# MCU_Design.net
KiCad netlist of a schematic drawn in EAGLE
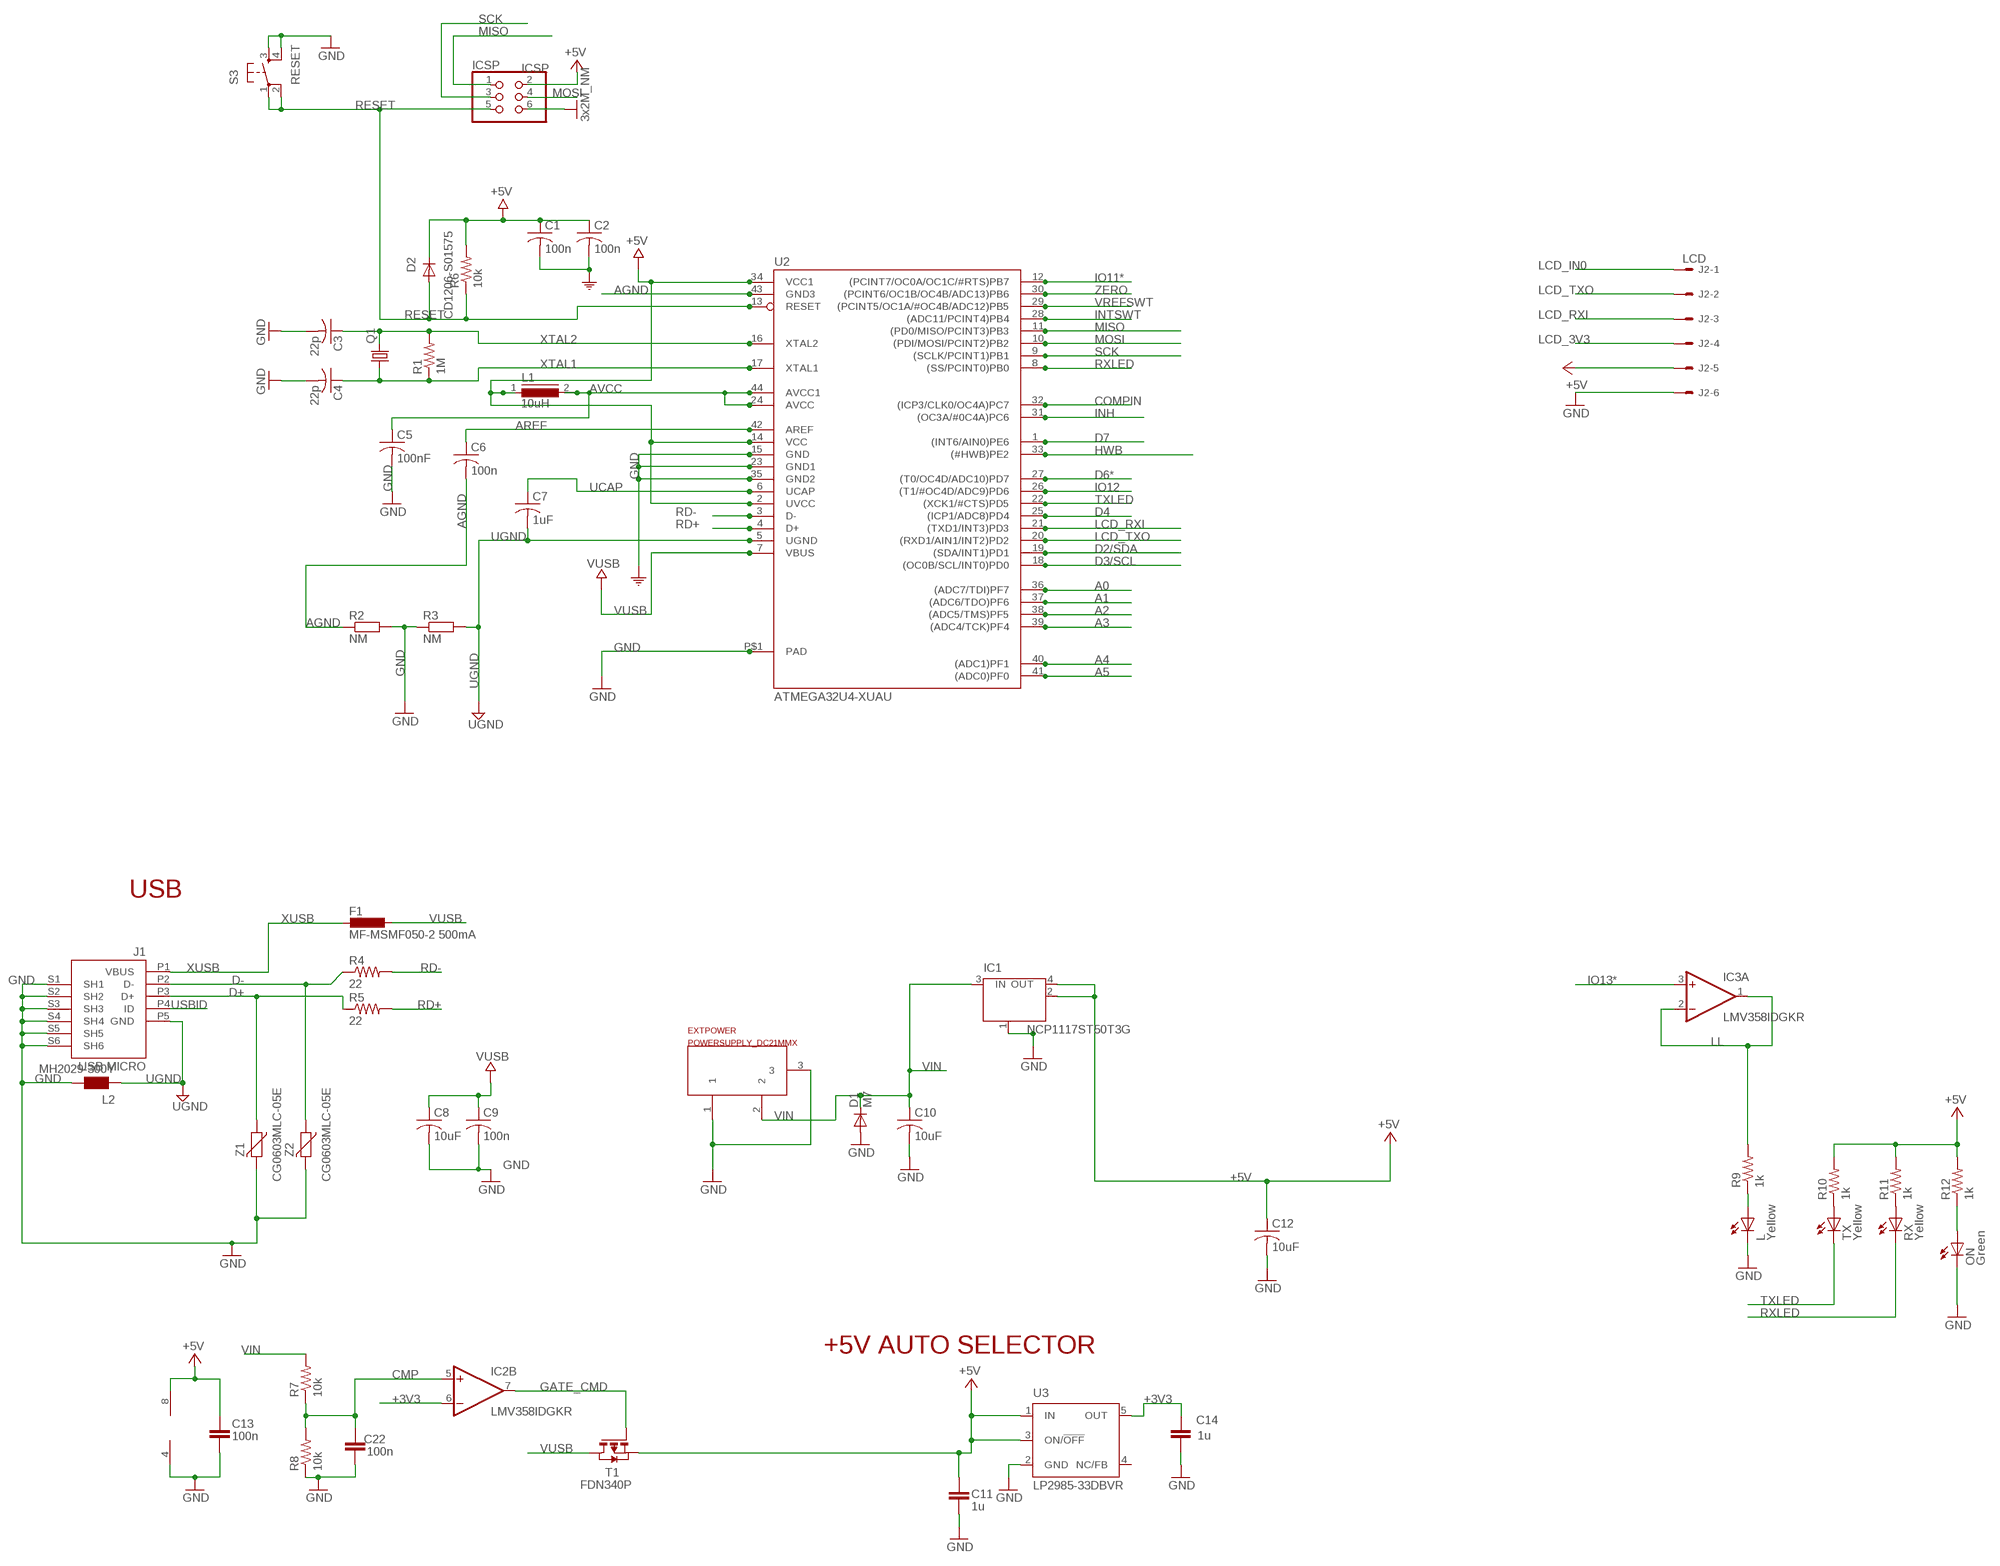
[diagram p0: schematic, sheet 1]

(export (version "E")
  (design (tool "Eeschema 10.0.6"))
  (components
    (comp (ref "C1")
      (value "100n")
      (footprint "eagle-import:C0805")
      (libsource (lib "eagle-import") (part "C-USC0805"))
    )
    (comp (ref "C2")
      (value "100n")
      (footprint "eagle-import:C0805")
      (libsource (lib "eagle-import") (part "C-USC0805"))
    )
    (comp (ref "C3")
      (value "22p")
      (footprint "eagle-import:C0805")
      (libsource (lib "eagle-import") (part "C-USC0805"))
    )
    (comp (ref "C4")
      (value "22p")
      (footprint "eagle-import:C0805")
      (libsource (lib "eagle-import") (part "C-USC0805"))
    )
    (comp (ref "C5")
      (value "100nF")
      (footprint "eagle-import:C0805")
      (libsource (lib "eagle-import") (part "C-USC0805"))
    )
    (comp (ref "C6")
      (value "100n")
      (footprint "eagle-import:C0805")
      (libsource (lib "eagle-import") (part "C-USC0805"))
    )
    (comp (ref "C7")
      (value "1uF")
      (footprint "eagle-import:C0805")
      (libsource (lib "eagle-import") (part "C-USC0805"))
    )
    (comp (ref "C8")
      (value "10uF")
      (footprint "eagle-import:C0805")
      (libsource (lib "eagle-import") (part "C-USC0805"))
    )
    (comp (ref "C9")
      (value "100n")
      (footprint "eagle-import:C0805")
      (libsource (lib "eagle-import") (part "C-USC0805"))
    )
    (comp (ref "C10")
      (value "10uF")
      (footprint "eagle-import:C0805")
      (libsource (lib "eagle-import") (part "C-USC0805"))
    )
    (comp (ref "C11")
      (value "1u")
      (footprint "eagle-import:C0603-ROUND")
      (libsource (lib "eagle-import") (part "C-EUC0603"))
    )
    (comp (ref "C12")
      (value "10uF")
      (footprint "eagle-import:C0805")
      (libsource (lib "eagle-import") (part "C-USC0805"))
    )
    (comp (ref "C13")
      (value "100n")
      (footprint "eagle-import:C0603-ROUND")
      (libsource (lib "eagle-import") (part "C-EUC0603"))
    )
    (comp (ref "C14")
      (value "1u")
      (footprint "eagle-import:C0603-ROUND")
      (libsource (lib "eagle-import") (part "C-EUC0603"))
    )
    (comp (ref "C22")
      (value "100n")
      (footprint "eagle-import:C0603-ROUND")
      (libsource (lib "eagle-import") (part "C-EUC0603"))
    )
    (comp (ref "D1")
      (value "M7")
      (footprint "eagle-import:SMB")
      (libsource (lib "eagle-import") (part "DIODE-SMB"))
    )
    (comp (ref "D2")
      (value "CD1206-S01575")
      (footprint "eagle-import:MINIMELF")
      (libsource (lib "eagle-import") (part "DIODE-MINIMELF"))
    )
    (comp (ref "EXTPOWER")
      (value "POWERSUPPLY_DC21MMX")
      (footprint "eagle-import:POWERSUPPLY_DC-21MM")
      (libsource (lib "eagle-import") (part "POWERSUPPLY_DC21MMX"))
    )
    (comp (ref "F1")
      (value "MF-MSMF050-2 500mA")
      (footprint "eagle-import:L1812")
      (libsource (lib "eagle-import") (part "L-EUL1812"))
    )
    (comp (ref "IC1")
      (value "NCP1117ST50T3G")
      (footprint "eagle-import:SOT223")
      (libsource (lib "eagle-import") (part "MC33269ST-3.3T3"))
    )
    (comp (ref "IC2")
      (value "LMV358IDGKR")
      (footprint "eagle-import:MSOP08")
      (libsource (lib "eagle-import") (part "LMV358?MMX"))
    )
    (comp (ref "IC3")
      (value "LMV358IDGKR")
      (footprint "eagle-import:MSOP08")
      (libsource (lib "eagle-import") (part "LMV358?MMX"))
    )
    (comp (ref "ICSP")
      (value "ICSP")
      (footprint "eagle-import:2X03")
      (libsource (lib "eagle-import") (part "PINHD-2X3"))
    )
    (comp (ref "J1")
      (value "USB MICRO")
      (footprint "eagle-import:CON2_USB_MICRO_B_AT")
      (libsource (lib "eagle-import") (part "MYCON2_USB-MINI-B"))
    )
    (comp (ref "J2")
      (value "LCD")
      (footprint "eagle-import:7395-06")
      (libsource (lib "eagle-import") (part "22-?-0605-7068"))
    )
    (comp (ref "L")
      (value "Yellow")
      (footprint "eagle-import:CHIPLED_0805")
      (libsource (lib "eagle-import") (part "LEDCHIPLED_0805"))
    )
    (comp (ref "L1")
      (value "10uH")
      (footprint "eagle-import:LBC15A")
      (libsource (lib "eagle-import") (part "LBC15A"))
    )
    (comp (ref "L2")
      (value "MH2029-300Y")
      (footprint "eagle-import:0805")
      (libsource (lib "eagle-import") (part "WE-CBF_0805"))
    )
    (comp (ref "ON")
      (value "Green")
      (footprint "eagle-import:CHIPLED_0805")
      (libsource (lib "eagle-import") (part "LEDCHIPLED_0805"))
    )
    (comp (ref "Q1")
      (value "CRYSTALHC49UP")
      (footprint "eagle-import:HC49UP")
      (libsource (lib "eagle-import") (part "CRYSTALHC49UP"))
    )
    (comp (ref "R1")
      (value "1M")
      (footprint "eagle-import:R0805")
      (libsource (lib "eagle-import") (part "R-US_R0805"))
    )
    (comp (ref "R2")
      (value "NM")
      (footprint "eagle-import:R0402")
      (libsource (lib "eagle-import") (part "R-EU_R0402"))
    )
    (comp (ref "R3")
      (value "NM")
      (footprint "eagle-import:R0402")
      (libsource (lib "eagle-import") (part "R-EU_R0402"))
    )
    (comp (ref "R4")
      (value "22")
      (footprint "eagle-import:R0805")
      (libsource (lib "eagle-import") (part "R-US_R0805"))
    )
    (comp (ref "R5")
      (value "22")
      (footprint "eagle-import:R0805")
      (libsource (lib "eagle-import") (part "R-US_R0805"))
    )
    (comp (ref "R6")
      (value "10k")
      (footprint "eagle-import:R0805")
      (libsource (lib "eagle-import") (part "R-US_R0805"))
    )
    (comp (ref "R7")
      (value "10k")
      (footprint "eagle-import:R0805")
      (libsource (lib "eagle-import") (part "R-US_R0805"))
    )
    (comp (ref "R8")
      (value "10k")
      (footprint "eagle-import:R0805")
      (libsource (lib "eagle-import") (part "R-US_R0805"))
    )
    (comp (ref "R9")
      (value "1k")
      (footprint "eagle-import:R0805")
      (libsource (lib "eagle-import") (part "R-US_R0805"))
    )
    (comp (ref "R10")
      (value "1k")
      (footprint "eagle-import:R0805")
      (libsource (lib "eagle-import") (part "R-US_R0805"))
    )
    (comp (ref "R11")
      (value "1k")
      (footprint "eagle-import:R0805")
      (libsource (lib "eagle-import") (part "R-US_R0805"))
    )
    (comp (ref "R12")
      (value "1k")
      (footprint "eagle-import:R0805")
      (libsource (lib "eagle-import") (part "R-US_R0805"))
    )
    (comp (ref "RX")
      (value "Yellow")
      (footprint "eagle-import:CHIPLED_0805")
      (libsource (lib "eagle-import") (part "LEDCHIPLED_0805"))
    )
    (comp (ref "S3")
      (value "RESET")
      (footprint "eagle-import:TACTILE_SWITCH_SMD")
      (libsource (lib "eagle-import") (part "TAC_SWITCHSMD"))
    )
    (comp (ref "T1")
      (value "FDN340P")
      (footprint "eagle-import:SOT-23")
      (libsource (lib "eagle-import") (part "PMOSSOT23"))
    )
    (comp (ref "TX")
      (value "Yellow")
      (footprint "eagle-import:CHIPLED_0805")
      (libsource (lib "eagle-import") (part "LEDCHIPLED_0805"))
    )
    (comp (ref "U2")
      (value "ATMEGA32U4-XUAU")
      (footprint "eagle-import:TQFP44-PAD")
      (libsource (lib "eagle-import") (part "ATMEGA32U4-XUAU"))
    )
    (comp (ref "U3")
      (value "LP2985-33DBVR")
      (footprint "eagle-import:SOT23-DBV")
      (libsource (lib "eagle-import") (part "LP2985-XXDBVR33"))
    )
    (comp (ref "Z1")
      (value "CG0603MLC-05E")
      (footprint "eagle-import:CT_CN0603")
      (libsource (lib "eagle-import") (part "VARISTORCN0603"))
    )
    (comp (ref "Z2")
      (value "CG0603MLC-05E")
      (footprint "eagle-import:CT_CN0603")
      (libsource (lib "eagle-import") (part "VARISTORCN0603"))
    )
  )
  (nets
    (net (code "1") (name "+5V") (class "Default")
      (node (ref "C1") (pin "1") (pinfunction "1_1") (pintype "passive"))
      (node (ref "C11") (pin "2") (pinfunction "2_2") (pintype "passive"))
      (node (ref "C12") (pin "1") (pinfunction "1_1") (pintype "passive"))
      (node (ref "C13") (pin "1") (pinfunction "1_1") (pintype "passive"))
      (node (ref "C2") (pin "1") (pinfunction "1_1") (pintype "passive"))
      (node (ref "D2") (pin "C") (pinfunction "C_C") (pintype "passive"))
      (node (ref "IC1") (pin "2") (pinfunction "OUT_2") (pintype "passive"))
      (node (ref "IC1") (pin "4") (pinfunction "OUT_4") (pintype "passive"))
      (node (ref "IC2") (pin "8") (pinfunction "V+_8") (pintype "power_in"))
      (node (ref "ICSP") (pin "2") (pinfunction "2_2") (pintype "passive"))
      (node (ref "J2") (pin "5") (pinfunction "S_5") (pintype "passive"))
      (node (ref "L1") (pin "1") (pinfunction "1_1") (pintype "passive"))
      (node (ref "R10") (pin "2") (pinfunction "2_2") (pintype "passive"))
      (node (ref "R11") (pin "2") (pinfunction "2_2") (pintype "passive"))
      (node (ref "R12") (pin "2") (pinfunction "2_2") (pintype "passive"))
      (node (ref "R6") (pin "2") (pinfunction "2_2") (pintype "passive"))
      (node (ref "T1") (pin "2") (pinfunction "S_2") (pintype "passive"))
      (node (ref "U2") (pin "14") (pinfunction "VCC_14") (pintype "power_in"))
      (node (ref "U2") (pin "2") (pinfunction "UVCC_2") (pintype "power_in"))
      (node (ref "U2") (pin "34") (pinfunction "VCC1_34") (pintype "power_in"))
      (node (ref "U3") (pin "1") (pinfunction "IN_1") (pintype "input"))
      (node (ref "U3") (pin "3") (pinfunction "ON/~{OFF}_3") (pintype "input"))
    )
    (net (code "2") (name "/+3V3") (class "Default")
      (node (ref "C14") (pin "2") (pinfunction "2_2") (pintype "passive"))
      (node (ref "IC2") (pin "6") (pinfunction "-IN_6") (pintype "input"))
      (node (ref "U3") (pin "5") (pinfunction "OUT_5") (pintype "passive"))
    )
    (net (code "3") (name "/A0") (class "Default")
      (node (ref "U2") (pin "36") (pinfunction "(ADC7/TDI)PF7_36") (pintype "bidirectional"))
    )
    (net (code "4") (name "/A1") (class "Default")
      (node (ref "U2") (pin "37") (pinfunction "(ADC6/TDO)PF6_37") (pintype "bidirectional"))
    )
    (net (code "5") (name "/A2") (class "Default")
      (node (ref "U2") (pin "38") (pinfunction "(ADC5/TMS)PF5_38") (pintype "bidirectional"))
    )
    (net (code "6") (name "/A3") (class "Default")
      (node (ref "U2") (pin "39") (pinfunction "(ADC4/TCK)PF4_39") (pintype "bidirectional"))
    )
    (net (code "7") (name "/A4") (class "Default")
      (node (ref "U2") (pin "40") (pinfunction "(ADC1)PF1_40") (pintype "bidirectional"))
    )
    (net (code "8") (name "/A5") (class "Default")
      (node (ref "U2") (pin "41") (pinfunction "(ADC0)PF0_41") (pintype "bidirectional"))
    )
    (net (code "9") (name "/AGND") (class "Default")
      (node (ref "C6") (pin "2") (pinfunction "2_2") (pintype "passive"))
      (node (ref "R2") (pin "1") (pinfunction "1_1") (pintype "passive"))
      (node (ref "U2") (pin "43") (pinfunction "GND3_43") (pintype "power_in"))
    )
    (net (code "10") (name "/AREF") (class "Default")
      (node (ref "C6") (pin "1") (pinfunction "1_1") (pintype "passive"))
      (node (ref "U2") (pin "42") (pinfunction "AREF_42") (pintype "power_in"))
    )
    (net (code "11") (name "/AVCC") (class "Default")
      (node (ref "C5") (pin "1") (pinfunction "1_1") (pintype "passive"))
      (node (ref "L1") (pin "2") (pinfunction "2_2") (pintype "passive"))
      (node (ref "U2") (pin "24") (pinfunction "AVCC_24") (pintype "power_in"))
      (node (ref "U2") (pin "44") (pinfunction "AVCC1_44") (pintype "power_in"))
    )
    (net (code "12") (name "/CMP") (class "Default")
      (node (ref "C22") (pin "2") (pinfunction "2_2") (pintype "passive"))
      (node (ref "IC2") (pin "5") (pinfunction "+IN_5") (pintype "input"))
      (node (ref "R7") (pin "1") (pinfunction "1_1") (pintype "passive"))
      (node (ref "R8") (pin "2") (pinfunction "2_2") (pintype "passive"))
    )
    (net (code "13") (name "/COMPIN") (class "Default")
      (node (ref "U2") (pin "32") (pinfunction "(ICP3/CLK0/OC4A)PC7_32") (pintype "bidirectional"))
    )
    (net (code "14") (name "/D+") (class "Default")
      (node (ref "J1") (pin "P3") (pinfunction "D+_P3") (pintype "bidirectional"))
      (node (ref "R5") (pin "1") (pinfunction "1_1") (pintype "passive"))
      (node (ref "Z1") (pin "1") (pinfunction "1_1") (pintype "passive"))
    )
    (net (code "15") (name "/D-") (class "Default")
      (node (ref "J1") (pin "P2") (pinfunction "D-_P2") (pintype "bidirectional"))
      (node (ref "R4") (pin "1") (pinfunction "1_1") (pintype "passive"))
      (node (ref "Z2") (pin "1") (pinfunction "1_1") (pintype "passive"))
    )
    (net (code "16") (name "/D2{slash}SDA") (class "Default")
      (node (ref "U2") (pin "19") (pinfunction "(SDA/INT1)PD1_19") (pintype "bidirectional"))
    )
    (net (code "17") (name "/D3{slash}SCL") (class "Default")
      (node (ref "U2") (pin "18") (pinfunction "(OC0B/SCL/INT0)PD0_18") (pintype "bidirectional"))
    )
    (net (code "18") (name "/D4") (class "Default")
      (node (ref "U2") (pin "25") (pinfunction "(ICP1/ADC8)PD4_25") (pintype "bidirectional"))
    )
    (net (code "19") (name "/D6*") (class "Default")
      (node (ref "U2") (pin "27") (pinfunction "(T0/OC4D/ADC10)PD7_27") (pintype "bidirectional"))
    )
    (net (code "20") (name "/D7") (class "Default")
      (node (ref "U2") (pin "1") (pinfunction "(INT6/AIN0)PE6_1") (pintype "bidirectional"))
    )
    (net (code "21") (name "/GATE_CMD") (class "Default")
      (node (ref "IC2") (pin "7") (pinfunction "OUT_7") (pintype "output"))
      (node (ref "T1") (pin "3") (pinfunction "G_3") (pintype "passive"))
    )
    (net (code "22") (name "/HWB") (class "Default")
      (node (ref "U2") (pin "33") (pinfunction "(#HWB)PE2_33") (pintype "bidirectional"))
    )
    (net (code "23") (name "/INH") (class "Default")
      (node (ref "U2") (pin "31") (pinfunction "(OC3A/#0C4A)PC6_31") (pintype "bidirectional"))
    )
    (net (code "24") (name "/INTSWT") (class "Default")
      (node (ref "U2") (pin "28") (pinfunction "(ADC11/PCINT4)PB4_28") (pintype "bidirectional"))
    )
    (net (code "25") (name "/IO11*") (class "Default")
      (node (ref "U2") (pin "12") (pinfunction "(PCINT7/OC0A/OC1C/#RTS)PB7_12") (pintype "bidirectional"))
    )
    (net (code "26") (name "/IO12") (class "Default")
      (node (ref "U2") (pin "26") (pinfunction "(T1/#OC4D/ADC9)PD6_26") (pintype "bidirectional"))
    )
    (net (code "27") (name "/IO13*") (class "Default")
      (node (ref "IC3") (pin "3") (pinfunction "+IN_3") (pintype "input"))
    )
    (net (code "28") (name "/LCD_3V3") (class "Default")
      (node (ref "J2") (pin "4") (pinfunction "S_4") (pintype "passive"))
    )
    (net (code "29") (name "/LCD_IN0") (class "Default")
      (node (ref "J2") (pin "1") (pinfunction "S_1") (pintype "passive"))
    )
    (net (code "30") (name "/LCD_RXI") (class "Default")
      (node (ref "J2") (pin "3") (pinfunction "S_3") (pintype "passive"))
      (node (ref "U2") (pin "21") (pinfunction "(TXD1/INT3)PD3_21") (pintype "bidirectional"))
    )
    (net (code "31") (name "/LCD_TXO") (class "Default")
      (node (ref "J2") (pin "2") (pinfunction "S_2") (pintype "passive"))
      (node (ref "U2") (pin "20") (pinfunction "(RXD1/AIN1/INT2)PD2_20") (pintype "bidirectional"))
    )
    (net (code "32") (name "/LL") (class "Default")
      (node (ref "IC3") (pin "1") (pinfunction "OUT_1") (pintype "output"))
      (node (ref "IC3") (pin "2") (pinfunction "-IN_2") (pintype "input"))
      (node (ref "R9") (pin "2") (pinfunction "2_2") (pintype "passive"))
    )
    (net (code "33") (name "/MISO") (class "Default")
      (node (ref "ICSP") (pin "1") (pinfunction "1_1") (pintype "passive"))
      (node (ref "U2") (pin "11") (pinfunction "(PD0/MISO/PCINT3)PB3_11") (pintype "bidirectional"))
    )
    (net (code "34") (name "/MOSI") (class "Default")
      (node (ref "ICSP") (pin "4") (pinfunction "4_4") (pintype "passive"))
      (node (ref "U2") (pin "10") (pinfunction "(PDI/MOSI/PCINT2)PB2_10") (pintype "bidirectional"))
    )
    (net (code "35") (name "/RD+") (class "Default")
      (node (ref "R5") (pin "2") (pinfunction "2_2") (pintype "passive"))
      (node (ref "U2") (pin "4") (pinfunction "D+_4") (pintype "bidirectional"))
    )
    (net (code "36") (name "/RD-") (class "Default")
      (node (ref "R4") (pin "2") (pinfunction "2_2") (pintype "passive"))
      (node (ref "U2") (pin "3") (pinfunction "D-_3") (pintype "bidirectional"))
    )
    (net (code "37") (name "/RESET") (class "Default")
      (node (ref "D2") (pin "A") (pinfunction "A_A") (pintype "passive"))
      (node (ref "ICSP") (pin "5") (pinfunction "5_5") (pintype "passive"))
      (node (ref "R6") (pin "1") (pinfunction "1_1") (pintype "passive"))
      (node (ref "S3") (pin "1") (pinfunction "1_1") (pintype "passive"))
      (node (ref "S3") (pin "2") (pinfunction "2_2") (pintype "passive"))
      (node (ref "U2") (pin "13") (pinfunction "RESET_13") (pintype "input"))
    )
    (net (code "38") (name "/RXLED") (class "Default")
      (node (ref "RX") (pin "C") (pinfunction "C_C") (pintype "passive"))
      (node (ref "U2") (pin "8") (pinfunction "(SS/PCINT0)PB0_8") (pintype "bidirectional"))
    )
    (net (code "39") (name "/SCK") (class "Default")
      (node (ref "ICSP") (pin "3") (pinfunction "3_3") (pintype "passive"))
      (node (ref "U2") (pin "9") (pinfunction "(SCLK/PCINT1)PB1_9") (pintype "bidirectional"))
    )
    (net (code "40") (name "/TXLED") (class "Default")
      (node (ref "TX") (pin "C") (pinfunction "C_C") (pintype "passive"))
      (node (ref "U2") (pin "22") (pinfunction "(XCK1/#CTS)PD5_22") (pintype "bidirectional"))
    )
    (net (code "41") (name "/UCAP") (class "Default")
      (node (ref "C7") (pin "1") (pinfunction "1_1") (pintype "passive"))
      (node (ref "U2") (pin "6") (pinfunction "UCAP_6") (pintype "passive"))
    )
    (net (code "42") (name "/USBID") (class "Default")
      (node (ref "J1") (pin "P4") (pinfunction "ID_P4") (pintype "bidirectional"))
    )
    (net (code "43") (name "/VIN") (class "Default")
      (node (ref "C10") (pin "1") (pinfunction "1_1") (pintype "passive"))
      (node (ref "D1") (pin "C") (pinfunction "C_C") (pintype "passive"))
      (node (ref "EXTPOWER") (pin "2") (pinfunction "2_2") (pintype "power_in"))
      (node (ref "IC1") (pin "3") (pinfunction "IN_3") (pintype "input"))
      (node (ref "R7") (pin "2") (pinfunction "2_2") (pintype "passive"))
    )
    (net (code "44") (name "/VREFSWT") (class "Default")
      (node (ref "U2") (pin "29") (pinfunction "(PCINT5/OC1A/#OC4B/ADC12)PB5_29") (pintype "bidirectional"))
    )
    (net (code "45") (name "/XTAL1") (class "Default")
      (node (ref "C4") (pin "1") (pinfunction "1_1") (pintype "passive"))
      (node (ref "Q1") (pin "1") (pinfunction "1_1") (pintype "passive"))
      (node (ref "R1") (pin "1") (pinfunction "1_1") (pintype "passive"))
      (node (ref "U2") (pin "17") (pinfunction "XTAL1_17") (pintype "bidirectional"))
    )
    (net (code "46") (name "/XTAL2") (class "Default")
      (node (ref "C3") (pin "1") (pinfunction "1_1") (pintype "passive"))
      (node (ref "Q1") (pin "2") (pinfunction "2_2") (pintype "passive"))
      (node (ref "R1") (pin "2") (pinfunction "2_2") (pintype "passive"))
      (node (ref "U2") (pin "16") (pinfunction "XTAL2_16") (pintype "bidirectional"))
    )
    (net (code "47") (name "/XUSB") (class "Default")
      (node (ref "F1") (pin "2") (pinfunction "2_2") (pintype "passive"))
      (node (ref "J1") (pin "P1") (pinfunction "VBUS_P1") (pintype "power_in"))
    )
    (net (code "48") (name "/ZERO") (class "Default")
      (node (ref "U2") (pin "30") (pinfunction "(PCINT6/OC1B/OC4B/ADC13)PB6_30") (pintype "bidirectional"))
    )
    (net (code "49") (name "3x2M_NM") (class "Default")
      (node (ref "C1") (pin "2") (pinfunction "2_2") (pintype "passive"))
      (node (ref "C10") (pin "2") (pinfunction "2_2") (pintype "passive"))
      (node (ref "C11") (pin "1") (pinfunction "1_1") (pintype "passive"))
      (node (ref "C12") (pin "2") (pinfunction "2_2") (pintype "passive"))
      (node (ref "C13") (pin "2") (pinfunction "2_2") (pintype "passive"))
      (node (ref "C14") (pin "1") (pinfunction "1_1") (pintype "passive"))
      (node (ref "C2") (pin "2") (pinfunction "2_2") (pintype "passive"))
      (node (ref "C22") (pin "1") (pinfunction "1_1") (pintype "passive"))
      (node (ref "C3") (pin "2") (pinfunction "2_2") (pintype "passive"))
      (node (ref "C4") (pin "2") (pinfunction "2_2") (pintype "passive"))
      (node (ref "C5") (pin "2") (pinfunction "2_2") (pintype "passive"))
      (node (ref "C8") (pin "2") (pinfunction "2_2") (pintype "passive"))
      (node (ref "C9") (pin "2") (pinfunction "2_2") (pintype "passive"))
      (node (ref "D1") (pin "A") (pinfunction "A_A") (pintype "passive"))
      (node (ref "EXTPOWER") (pin "1") (pinfunction "1_1") (pintype "power_in"))
      (node (ref "EXTPOWER") (pin "3") (pinfunction "3_3") (pintype "power_in"))
      (node (ref "IC1") (pin "1") (pinfunction "GND/ADJ_1") (pintype "input"))
      (node (ref "IC2") (pin "4") (pinfunction "V-_4") (pintype "power_in"))
      (node (ref "ICSP") (pin "6") (pinfunction "6_6") (pintype "passive"))
      (node (ref "J1") (pin "S1") (pinfunction "SH1_S1") (pintype "passive"))
      (node (ref "J1") (pin "S2") (pinfunction "SH2_S2") (pintype "passive"))
      (node (ref "J1") (pin "S3") (pinfunction "SH3_S3") (pintype "passive"))
      (node (ref "J1") (pin "S4") (pinfunction "SH4_S4") (pintype "passive"))
      (node (ref "J1") (pin "S5") (pinfunction "SH5_S5") (pintype "passive"))
      (node (ref "J1") (pin "S6") (pinfunction "SH6_S6") (pintype "passive"))
      (node (ref "J2") (pin "6") (pinfunction "S_6") (pintype "passive"))
      (node (ref "L") (pin "C") (pinfunction "C_C") (pintype "passive"))
      (node (ref "L2") (pin "2") (pinfunction "2_2") (pintype "passive"))
      (node (ref "ON") (pin "C") (pinfunction "C_C") (pintype "passive"))
      (node (ref "R2") (pin "2") (pinfunction "2_2") (pintype "passive"))
      (node (ref "R3") (pin "1") (pinfunction "1_1") (pintype "passive"))
      (node (ref "R8") (pin "1") (pinfunction "1_1") (pintype "passive"))
      (node (ref "S3") (pin "3") (pinfunction "3_3") (pintype "passive"))
      (node (ref "S3") (pin "4") (pinfunction "4_4") (pintype "passive"))
      (node (ref "U2") (pin "15") (pinfunction "GND_15") (pintype "power_in"))
      (node (ref "U2") (pin "23") (pinfunction "GND1_23") (pintype "power_in"))
      (node (ref "U2") (pin "35") (pinfunction "GND2_35") (pintype "power_in"))
      (node (ref "U2") (pin "P$1") (pinfunction "PAD_P$1") (pintype "power_in"))
      (node (ref "U3") (pin "2") (pinfunction "GND_2") (pintype "power_in"))
      (node (ref "Z1") (pin "2") (pinfunction "2_2") (pintype "passive"))
      (node (ref "Z2") (pin "2") (pinfunction "2_2") (pintype "passive"))
    )
    (net (code "50") (name "Net-(L-PadA)") (class "Default")
      (node (ref "L") (pin "A") (pinfunction "A_A") (pintype "passive"))
      (node (ref "R9") (pin "1") (pinfunction "1_1") (pintype "passive"))
    )
    (net (code "51") (name "Net-(ON-PadA)") (class "Default")
      (node (ref "ON") (pin "A") (pinfunction "A_A") (pintype "passive"))
      (node (ref "R12") (pin "1") (pinfunction "1_1") (pintype "passive"))
    )
    (net (code "52") (name "Net-(R10-Pad1)") (class "Default")
      (node (ref "R10") (pin "1") (pinfunction "1_1") (pintype "passive"))
      (node (ref "TX") (pin "A") (pinfunction "A_A") (pintype "passive"))
    )
    (net (code "53") (name "Net-(R11-Pad1)") (class "Default")
      (node (ref "R11") (pin "1") (pinfunction "1_1") (pintype "passive"))
      (node (ref "RX") (pin "A") (pinfunction "A_A") (pintype "passive"))
    )
    (net (code "54") (name "UGND") (class "Default")
      (node (ref "C7") (pin "2") (pinfunction "2_2") (pintype "passive"))
      (node (ref "J1") (pin "P5") (pinfunction "GND_P5") (pintype "passive"))
      (node (ref "L2") (pin "1") (pinfunction "1_1") (pintype "passive"))
      (node (ref "R3") (pin "2") (pinfunction "2_2") (pintype "passive"))
      (node (ref "U2") (pin "5") (pinfunction "UGND_5") (pintype "power_in"))
    )
    (net (code "55") (name "VUSB") (class "Default")
      (node (ref "C8") (pin "1") (pinfunction "1_1") (pintype "passive"))
      (node (ref "C9") (pin "1") (pinfunction "1_1") (pintype "passive"))
      (node (ref "F1") (pin "1") (pinfunction "1_1") (pintype "passive"))
      (node (ref "T1") (pin "1") (pinfunction "D_1") (pintype "passive"))
      (node (ref "U2") (pin "7") (pinfunction "VBUS_7") (pintype "input"))
    )
    (net (code "56") (name "unconnected-(U3-NC{slash}FB-Pad4)") (class "Default")
      (node (ref "U3") (pin "4") (pinfunction "NC/FB_4") (pintype "passive"))
    )
  )
)
